# DW08B.net
KiCad netlist of a schematic drawn in EAGLE
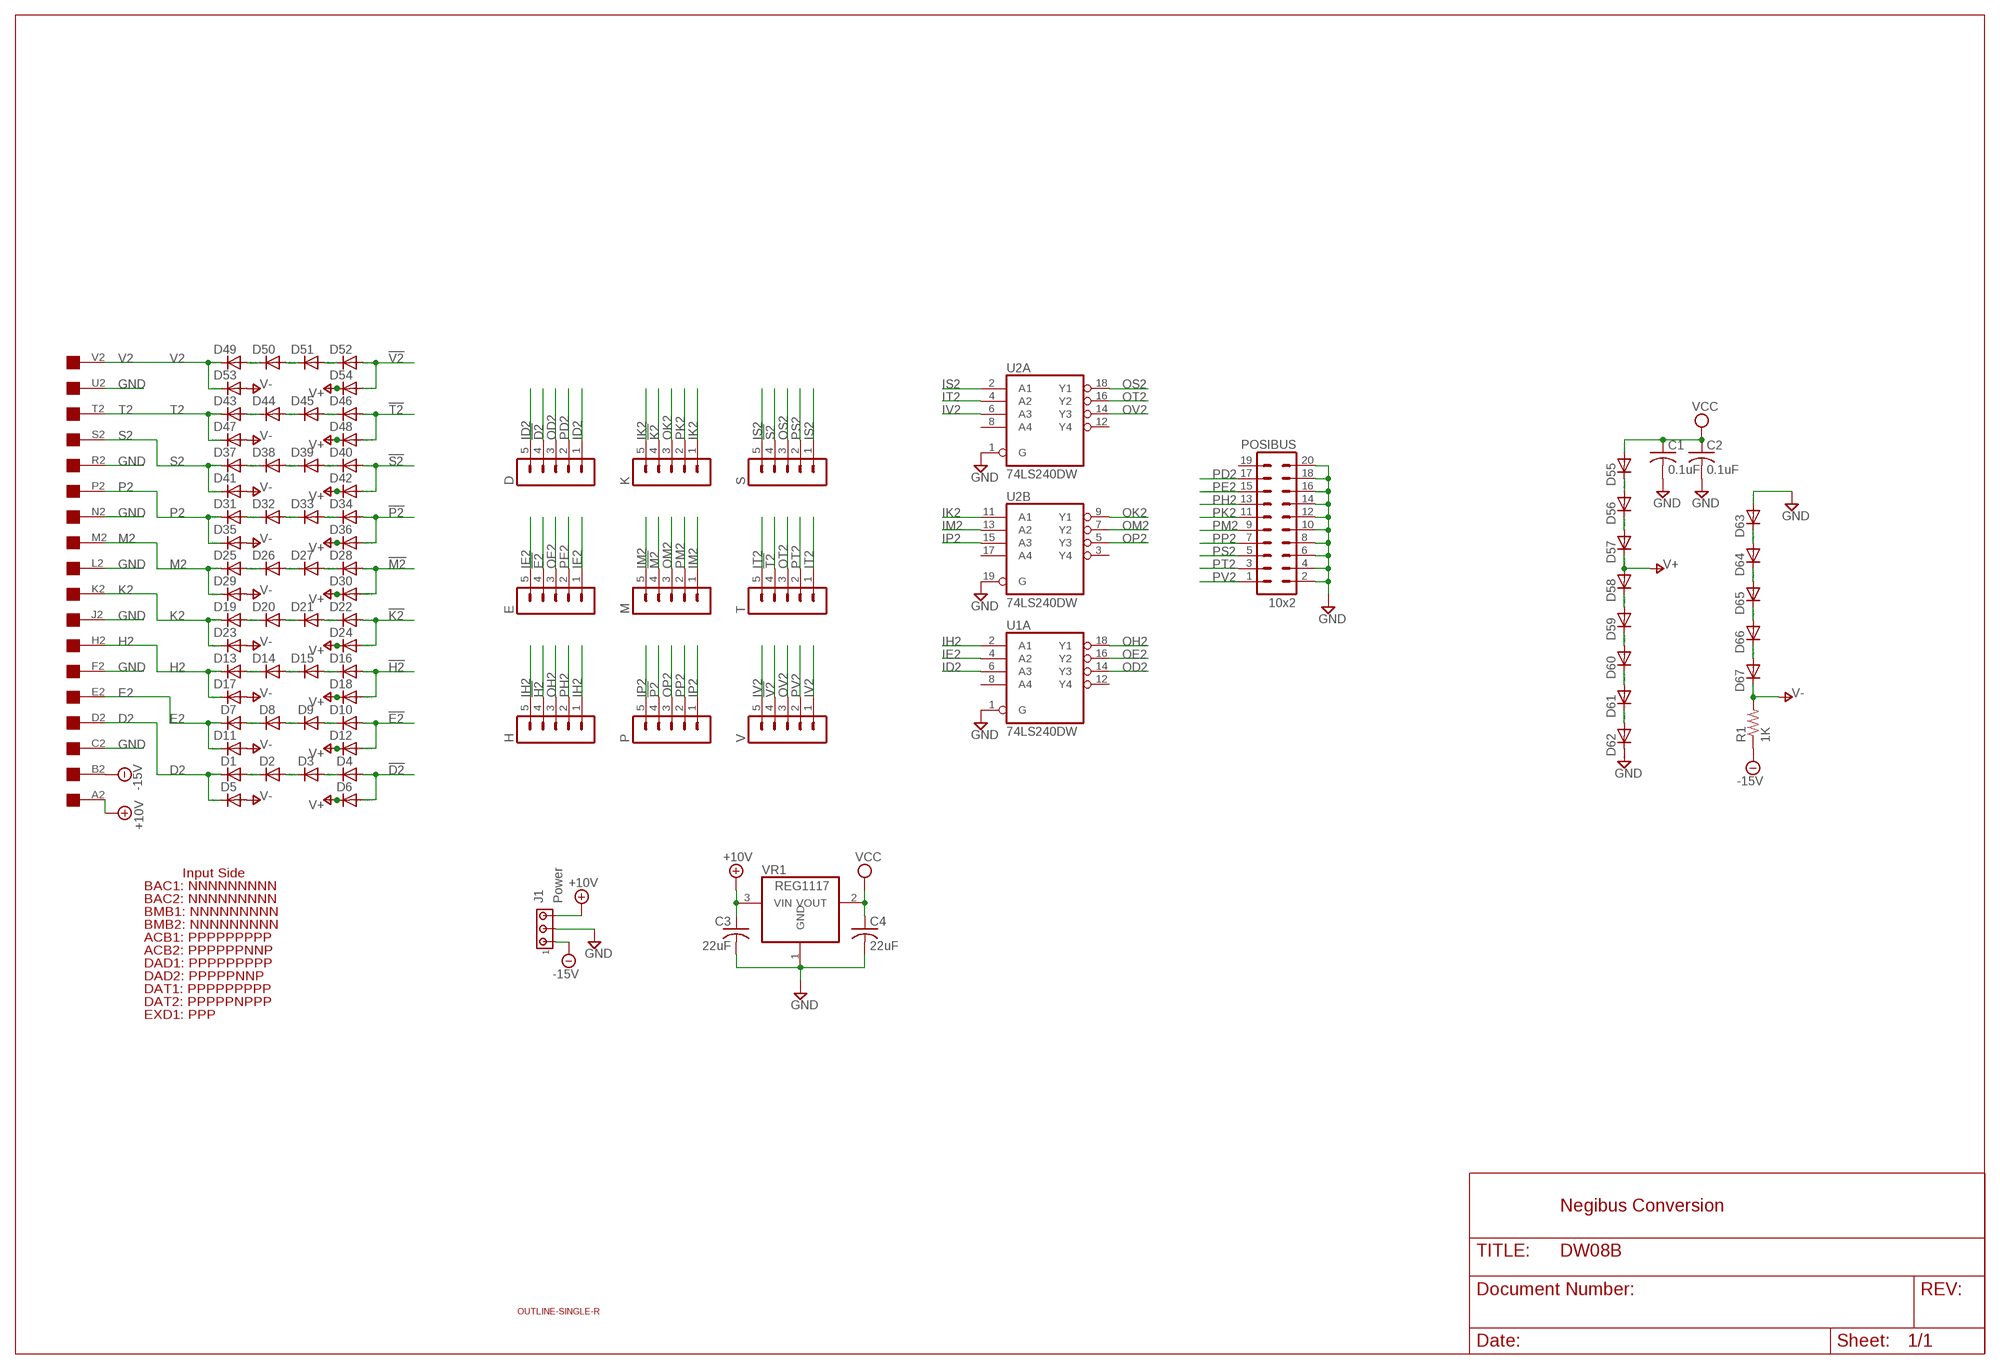
[diagram p0: schematic, sheet 1]

(export (version "E")
  (design (tool "Eeschema 10.0.6"))
  (components
    (comp (ref "C1")
      (value "0.1uF")
      (footprint "eagle-import:C050-025X075")
      (libsource (lib "eagle-import") (part "C-US050-025X075"))
    )
    (comp (ref "C2")
      (value "0.1uF")
      (footprint "eagle-import:C050-025X075")
      (libsource (lib "eagle-import") (part "C-US050-025X075"))
    )
    (comp (ref "C3")
      (value "22uF")
      (footprint "eagle-import:C0805")
      (libsource (lib "eagle-import") (part "C-USC0805"))
    )
    (comp (ref "C4")
      (value "22uF")
      (footprint "eagle-import:C0805")
      (libsource (lib "eagle-import") (part "C-USC0805"))
    )
    (comp (ref "D")
      (value "MA05-1")
      (footprint "eagle-import:MA05-1")
      (libsource (lib "eagle-import") (part "MA05-1"))
    )
    (comp (ref "D1")
      (value "1N4148WS")
      (footprint "eagle-import:SOD323-W")
      (libsource (lib "eagle-import") (part "DIODE-SOD323-W"))
    )
    (comp (ref "D2")
      (value "1N4148WS")
      (footprint "eagle-import:SOD323-W")
      (libsource (lib "eagle-import") (part "DIODE-SOD323-W"))
    )
    (comp (ref "D3")
      (value "1N4148WS")
      (footprint "eagle-import:SOD323-W")
      (libsource (lib "eagle-import") (part "DIODE-SOD323-W"))
    )
    (comp (ref "D4")
      (value "1N4148WS")
      (footprint "eagle-import:SOD323-W")
      (libsource (lib "eagle-import") (part "DIODE-SOD323-W"))
    )
    (comp (ref "D5")
      (value "1N4148WS")
      (footprint "eagle-import:SOD323-W")
      (libsource (lib "eagle-import") (part "DIODE-SOD323-W"))
    )
    (comp (ref "D6")
      (value "1N4148WS")
      (footprint "eagle-import:SOD323-W")
      (libsource (lib "eagle-import") (part "DIODE-SOD323-W"))
    )
    (comp (ref "D7")
      (value "1N4148WS")
      (footprint "eagle-import:SOD323-W")
      (libsource (lib "eagle-import") (part "DIODE-SOD323-W"))
    )
    (comp (ref "D8")
      (value "1N4148WS")
      (footprint "eagle-import:SOD323-W")
      (libsource (lib "eagle-import") (part "DIODE-SOD323-W"))
    )
    (comp (ref "D9")
      (value "1N4148WS")
      (footprint "eagle-import:SOD323-W")
      (libsource (lib "eagle-import") (part "DIODE-SOD323-W"))
    )
    (comp (ref "D10")
      (value "1N4148WS")
      (footprint "eagle-import:SOD323-W")
      (libsource (lib "eagle-import") (part "DIODE-SOD323-W"))
    )
    (comp (ref "D11")
      (value "1N4148WS")
      (footprint "eagle-import:SOD323-W")
      (libsource (lib "eagle-import") (part "DIODE-SOD323-W"))
    )
    (comp (ref "D12")
      (value "1N4148WS")
      (footprint "eagle-import:SOD323-W")
      (libsource (lib "eagle-import") (part "DIODE-SOD323-W"))
    )
    (comp (ref "D13")
      (value "1N4148WS")
      (footprint "eagle-import:SOD323-W")
      (libsource (lib "eagle-import") (part "DIODE-SOD323-W"))
    )
    (comp (ref "D14")
      (value "1N4148WS")
      (footprint "eagle-import:SOD323-W")
      (libsource (lib "eagle-import") (part "DIODE-SOD323-W"))
    )
    (comp (ref "D15")
      (value "1N4148WS")
      (footprint "eagle-import:SOD323-W")
      (libsource (lib "eagle-import") (part "DIODE-SOD323-W"))
    )
    (comp (ref "D16")
      (value "1N4148WS")
      (footprint "eagle-import:SOD323-W")
      (libsource (lib "eagle-import") (part "DIODE-SOD323-W"))
    )
    (comp (ref "D17")
      (value "1N4148WS")
      (footprint "eagle-import:SOD323-W")
      (libsource (lib "eagle-import") (part "DIODE-SOD323-W"))
    )
    (comp (ref "D18")
      (value "1N4148WS")
      (footprint "eagle-import:SOD323-W")
      (libsource (lib "eagle-import") (part "DIODE-SOD323-W"))
    )
    (comp (ref "D19")
      (value "1N4148WS")
      (footprint "eagle-import:SOD323-W")
      (libsource (lib "eagle-import") (part "DIODE-SOD323-W"))
    )
    (comp (ref "D20")
      (value "1N4148WS")
      (footprint "eagle-import:SOD323-W")
      (libsource (lib "eagle-import") (part "DIODE-SOD323-W"))
    )
    (comp (ref "D21")
      (value "1N4148WS")
      (footprint "eagle-import:SOD323-W")
      (libsource (lib "eagle-import") (part "DIODE-SOD323-W"))
    )
    (comp (ref "D22")
      (value "1N4148WS")
      (footprint "eagle-import:SOD323-W")
      (libsource (lib "eagle-import") (part "DIODE-SOD323-W"))
    )
    (comp (ref "D23")
      (value "1N4148WS")
      (footprint "eagle-import:SOD323-W")
      (libsource (lib "eagle-import") (part "DIODE-SOD323-W"))
    )
    (comp (ref "D24")
      (value "1N4148WS")
      (footprint "eagle-import:SOD323-W")
      (libsource (lib "eagle-import") (part "DIODE-SOD323-W"))
    )
    (comp (ref "D25")
      (value "1N4148WS")
      (footprint "eagle-import:SOD323-W")
      (libsource (lib "eagle-import") (part "DIODE-SOD323-W"))
    )
    (comp (ref "D26")
      (value "1N4148WS")
      (footprint "eagle-import:SOD323-W")
      (libsource (lib "eagle-import") (part "DIODE-SOD323-W"))
    )
    (comp (ref "D27")
      (value "1N4148WS")
      (footprint "eagle-import:SOD323-W")
      (libsource (lib "eagle-import") (part "DIODE-SOD323-W"))
    )
    (comp (ref "D28")
      (value "1N4148WS")
      (footprint "eagle-import:SOD323-W")
      (libsource (lib "eagle-import") (part "DIODE-SOD323-W"))
    )
    (comp (ref "D29")
      (value "1N4148WS")
      (footprint "eagle-import:SOD323-W")
      (libsource (lib "eagle-import") (part "DIODE-SOD323-W"))
    )
    (comp (ref "D30")
      (value "1N4148WS")
      (footprint "eagle-import:SOD323-W")
      (libsource (lib "eagle-import") (part "DIODE-SOD323-W"))
    )
    (comp (ref "D31")
      (value "1N4148WS")
      (footprint "eagle-import:SOD323-W")
      (libsource (lib "eagle-import") (part "DIODE-SOD323-W"))
    )
    (comp (ref "D32")
      (value "1N4148WS")
      (footprint "eagle-import:SOD323-W")
      (libsource (lib "eagle-import") (part "DIODE-SOD323-W"))
    )
    (comp (ref "D33")
      (value "1N4148WS")
      (footprint "eagle-import:SOD323-W")
      (libsource (lib "eagle-import") (part "DIODE-SOD323-W"))
    )
    (comp (ref "D34")
      (value "1N4148WS")
      (footprint "eagle-import:SOD323-W")
      (libsource (lib "eagle-import") (part "DIODE-SOD323-W"))
    )
    (comp (ref "D35")
      (value "1N4148WS")
      (footprint "eagle-import:SOD323-W")
      (libsource (lib "eagle-import") (part "DIODE-SOD323-W"))
    )
    (comp (ref "D36")
      (value "1N4148WS")
      (footprint "eagle-import:SOD323-W")
      (libsource (lib "eagle-import") (part "DIODE-SOD323-W"))
    )
    (comp (ref "D37")
      (value "1N4148WS")
      (footprint "eagle-import:SOD323-W")
      (libsource (lib "eagle-import") (part "DIODE-SOD323-W"))
    )
    (comp (ref "D38")
      (value "1N4148WS")
      (footprint "eagle-import:SOD323-W")
      (libsource (lib "eagle-import") (part "DIODE-SOD323-W"))
    )
    (comp (ref "D39")
      (value "1N4148WS")
      (footprint "eagle-import:SOD323-W")
      (libsource (lib "eagle-import") (part "DIODE-SOD323-W"))
    )
    (comp (ref "D40")
      (value "1N4148WS")
      (footprint "eagle-import:SOD323-W")
      (libsource (lib "eagle-import") (part "DIODE-SOD323-W"))
    )
    (comp (ref "D41")
      (value "1N4148WS")
      (footprint "eagle-import:SOD323-W")
      (libsource (lib "eagle-import") (part "DIODE-SOD323-W"))
    )
    (comp (ref "D42")
      (value "1N4148WS")
      (footprint "eagle-import:SOD323-W")
      (libsource (lib "eagle-import") (part "DIODE-SOD323-W"))
    )
    (comp (ref "D43")
      (value "1N4148WS")
      (footprint "eagle-import:SOD323-W")
      (libsource (lib "eagle-import") (part "DIODE-SOD323-W"))
    )
    (comp (ref "D44")
      (value "1N4148WS")
      (footprint "eagle-import:SOD323-W")
      (libsource (lib "eagle-import") (part "DIODE-SOD323-W"))
    )
    (comp (ref "D45")
      (value "1N4148WS")
      (footprint "eagle-import:SOD323-W")
      (libsource (lib "eagle-import") (part "DIODE-SOD323-W"))
    )
    (comp (ref "D46")
      (value "1N4148WS")
      (footprint "eagle-import:SOD323-W")
      (libsource (lib "eagle-import") (part "DIODE-SOD323-W"))
    )
    (comp (ref "D47")
      (value "1N4148WS")
      (footprint "eagle-import:SOD323-W")
      (libsource (lib "eagle-import") (part "DIODE-SOD323-W"))
    )
    (comp (ref "D48")
      (value "1N4148WS")
      (footprint "eagle-import:SOD323-W")
      (libsource (lib "eagle-import") (part "DIODE-SOD323-W"))
    )
    (comp (ref "D49")
      (value "1N4148WS")
      (footprint "eagle-import:SOD323-W")
      (libsource (lib "eagle-import") (part "DIODE-SOD323-W"))
    )
    (comp (ref "D50")
      (value "1N4148WS")
      (footprint "eagle-import:SOD323-W")
      (libsource (lib "eagle-import") (part "DIODE-SOD323-W"))
    )
    (comp (ref "D51")
      (value "1N4148WS")
      (footprint "eagle-import:SOD323-W")
      (libsource (lib "eagle-import") (part "DIODE-SOD323-W"))
    )
    (comp (ref "D52")
      (value "1N4148WS")
      (footprint "eagle-import:SOD323-W")
      (libsource (lib "eagle-import") (part "DIODE-SOD323-W"))
    )
    (comp (ref "D53")
      (value "1N4148WS")
      (footprint "eagle-import:SOD323-W")
      (libsource (lib "eagle-import") (part "DIODE-SOD323-W"))
    )
    (comp (ref "D54")
      (value "1N4148WS")
      (footprint "eagle-import:SOD323-W")
      (libsource (lib "eagle-import") (part "DIODE-SOD323-W"))
    )
    (comp (ref "D55")
      (value "1N4148WS")
      (footprint "eagle-import:SOD323-W")
      (libsource (lib "eagle-import") (part "DIODE-SOD323-W"))
    )
    (comp (ref "D56")
      (value "1N4148WS")
      (footprint "eagle-import:SOD323-W")
      (libsource (lib "eagle-import") (part "DIODE-SOD323-W"))
    )
    (comp (ref "D57")
      (value "1N4148WS")
      (footprint "eagle-import:SOD323-W")
      (libsource (lib "eagle-import") (part "DIODE-SOD323-W"))
    )
    (comp (ref "D58")
      (value "1N4148WS")
      (footprint "eagle-import:SOD323-W")
      (libsource (lib "eagle-import") (part "DIODE-SOD323-W"))
    )
    (comp (ref "D59")
      (value "1N4148WS")
      (footprint "eagle-import:SOD323-W")
      (libsource (lib "eagle-import") (part "DIODE-SOD323-W"))
    )
    (comp (ref "D60")
      (value "1N4148WS")
      (footprint "eagle-import:SOD323-W")
      (libsource (lib "eagle-import") (part "DIODE-SOD323-W"))
    )
    (comp (ref "D61")
      (value "1N4148WS")
      (footprint "eagle-import:SOD323-W")
      (libsource (lib "eagle-import") (part "DIODE-SOD323-W"))
    )
    (comp (ref "D62")
      (value "1N4148WS")
      (footprint "eagle-import:SOD323-W")
      (libsource (lib "eagle-import") (part "DIODE-SOD323-W"))
    )
    (comp (ref "D63")
      (value "1N4148WS")
      (footprint "eagle-import:SOD323-W")
      (libsource (lib "eagle-import") (part "DIODE-SOD323-W"))
    )
    (comp (ref "D64")
      (value "1N4148WS")
      (footprint "eagle-import:SOD323-W")
      (libsource (lib "eagle-import") (part "DIODE-SOD323-W"))
    )
    (comp (ref "D65")
      (value "1N4148WS")
      (footprint "eagle-import:SOD323-W")
      (libsource (lib "eagle-import") (part "DIODE-SOD323-W"))
    )
    (comp (ref "D66")
      (value "1N4148WS")
      (footprint "eagle-import:SOD323-W")
      (libsource (lib "eagle-import") (part "DIODE-SOD323-W"))
    )
    (comp (ref "D67")
      (value "1N4148WS")
      (footprint "eagle-import:SOD323-W")
      (libsource (lib "eagle-import") (part "DIODE-SOD323-W"))
    )
    (comp (ref "E")
      (value "MA05-1")
      (footprint "eagle-import:MA05-1")
      (libsource (lib "eagle-import") (part "MA05-1"))
    )
    (comp (ref "H")
      (value "MA05-1")
      (footprint "eagle-import:MA05-1")
      (libsource (lib "eagle-import") (part "MA05-1"))
    )
    (comp (ref "J1")
      (value "Power")
      (footprint "eagle-import:10X03MTA")
      (libsource (lib "eagle-import") (part "MTA03-100"))
    )
    (comp (ref "K")
      (value "MA05-1")
      (footprint "eagle-import:MA05-1")
      (libsource (lib "eagle-import") (part "MA05-1"))
    )
    (comp (ref "M")
      (value "MA05-1")
      (footprint "eagle-import:MA05-1")
      (libsource (lib "eagle-import") (part "MA05-1"))
    )
    (comp (ref "P")
      (value "MA05-1")
      (footprint "eagle-import:MA05-1")
      (libsource (lib "eagle-import") (part "MA05-1"))
    )
    (comp (ref "POSIBUS")
      (value "10x2")
      (footprint "eagle-import:MA10-2")
      (libsource (lib "eagle-import") (part "MA10-2"))
    )
    (comp (ref "R1")
      (value "1K")
      (footprint "eagle-import:0207_10")
      (libsource (lib "eagle-import") (part "R-US_0207/10"))
    )
    (comp (ref "S")
      (value "MA05-1")
      (footprint "eagle-import:MA05-1")
      (libsource (lib "eagle-import") (part "MA05-1"))
    )
    (comp (ref "T")
      (value "MA05-1")
      (footprint "eagle-import:MA05-1")
      (libsource (lib "eagle-import") (part "MA05-1"))
    )
    (comp (ref "U$1")
      (value "OUTLINE-SINGLE-R")
      (footprint "eagle-import:SINGLE-R")
      (libsource (lib "eagle-import") (part "OUTLINE-SINGLE-R"))
    )
    (comp (ref "U$2")
      (value "EDGE")
      (footprint "eagle-import:EDGE-CON2")
      (libsource (lib "eagle-import") (part "SINGLE"))
    )
    (comp (ref "U1")
      (value "74LS240DW")
      (footprint "eagle-import:SO20W")
      (libsource (lib "eagle-import") (part "74240DWLS"))
    )
    (comp (ref "U2")
      (value "74LS240DW")
      (footprint "eagle-import:SO20W")
      (libsource (lib "eagle-import") (part "74240DWLS"))
    )
    (comp (ref "V")
      (value "MA05-1")
      (footprint "eagle-import:MA05-1")
      (libsource (lib "eagle-import") (part "MA05-1"))
    )
    (comp (ref "VR1")
      (value "REG1117")
      (footprint "eagle-import:SOT223")
      (libsource (lib "eagle-import") (part "REG1117"))
    )
  )
  (nets
    (net (code "1") (name "+10V") (class "Default")
      (node (ref "C3") (pin "1") (pinfunction "1_1") (pintype "passive"))
      (node (ref "J1") (pin "3") (pinfunction "3_3") (pintype "passive"))
      (node (ref "U$2") (pin "A2") (pinfunction "1_A2") (pintype "bidirectional"))
      (node (ref "VR1") (pin "3") (pinfunction "VIN_3") (pintype "input"))
    )
    (net (code "2") (name "-15V") (class "Default")
      (node (ref "J1") (pin "1") (pinfunction "1_1") (pintype "passive"))
      (node (ref "R1") (pin "1") (pinfunction "1_1") (pintype "passive"))
      (node (ref "U$2") (pin "B2") (pinfunction "1_B2") (pintype "bidirectional"))
    )
    (net (code "3") (name "/D2") (class "Default")
      (node (ref "D1") (pin "C") (pinfunction "C_C") (pintype "passive"))
      (node (ref "D5") (pin "C") (pinfunction "C_C") (pintype "passive"))
      (node (ref "U$2") (pin "D2") (pinfunction "1_D2") (pintype "bidirectional"))
    )
    (net (code "4") (name "/E2") (class "Default")
      (node (ref "D11") (pin "C") (pinfunction "C_C") (pintype "passive"))
      (node (ref "D7") (pin "C") (pinfunction "C_C") (pintype "passive"))
      (node (ref "U$2") (pin "E2") (pinfunction "1_E2") (pintype "bidirectional"))
    )
    (net (code "5") (name "/H2") (class "Default")
      (node (ref "D13") (pin "C") (pinfunction "C_C") (pintype "passive"))
      (node (ref "D17") (pin "C") (pinfunction "C_C") (pintype "passive"))
      (node (ref "U$2") (pin "H2") (pinfunction "1_H2") (pintype "bidirectional"))
    )
    (net (code "6") (name "/ID2") (class "Default")
      (node (ref "D") (pin "1") (pinfunction "1_1") (pintype "passive"))
      (node (ref "D") (pin "5") (pinfunction "5_5") (pintype "passive"))
      (node (ref "U1") (pin "6") (pinfunction "A3_6") (pintype "input"))
    )
    (net (code "7") (name "/IE2") (class "Default")
      (node (ref "E") (pin "1") (pinfunction "1_1") (pintype "passive"))
      (node (ref "E") (pin "5") (pinfunction "5_5") (pintype "passive"))
      (node (ref "U1") (pin "4") (pinfunction "A2_4") (pintype "input"))
    )
    (net (code "8") (name "/IH2") (class "Default")
      (node (ref "H") (pin "1") (pinfunction "1_1") (pintype "passive"))
      (node (ref "H") (pin "5") (pinfunction "5_5") (pintype "passive"))
      (node (ref "U1") (pin "2") (pinfunction "A1_2") (pintype "input"))
    )
    (net (code "9") (name "/IK2") (class "Default")
      (node (ref "K") (pin "1") (pinfunction "1_1") (pintype "passive"))
      (node (ref "K") (pin "5") (pinfunction "5_5") (pintype "passive"))
      (node (ref "U2") (pin "11") (pinfunction "A1_11") (pintype "input"))
    )
    (net (code "10") (name "/IM2") (class "Default")
      (node (ref "M") (pin "1") (pinfunction "1_1") (pintype "passive"))
      (node (ref "M") (pin "5") (pinfunction "5_5") (pintype "passive"))
      (node (ref "U2") (pin "13") (pinfunction "A2_13") (pintype "input"))
    )
    (net (code "11") (name "/IP2") (class "Default")
      (node (ref "P") (pin "1") (pinfunction "1_1") (pintype "passive"))
      (node (ref "P") (pin "5") (pinfunction "5_5") (pintype "passive"))
      (node (ref "U2") (pin "15") (pinfunction "A3_15") (pintype "input"))
    )
    (net (code "12") (name "/IS2") (class "Default")
      (node (ref "S") (pin "1") (pinfunction "1_1") (pintype "passive"))
      (node (ref "S") (pin "5") (pinfunction "5_5") (pintype "passive"))
      (node (ref "U2") (pin "2") (pinfunction "A1_2") (pintype "input"))
    )
    (net (code "13") (name "/IT2") (class "Default")
      (node (ref "T") (pin "1") (pinfunction "1_1") (pintype "passive"))
      (node (ref "T") (pin "5") (pinfunction "5_5") (pintype "passive"))
      (node (ref "U2") (pin "4") (pinfunction "A2_4") (pintype "input"))
    )
    (net (code "14") (name "/IV2") (class "Default")
      (node (ref "U2") (pin "6") (pinfunction "A3_6") (pintype "input"))
      (node (ref "V") (pin "1") (pinfunction "1_1") (pintype "passive"))
      (node (ref "V") (pin "5") (pinfunction "5_5") (pintype "passive"))
    )
    (net (code "15") (name "/K2") (class "Default")
      (node (ref "D19") (pin "C") (pinfunction "C_C") (pintype "passive"))
      (node (ref "D23") (pin "C") (pinfunction "C_C") (pintype "passive"))
      (node (ref "U$2") (pin "K2") (pinfunction "1_K2") (pintype "bidirectional"))
    )
    (net (code "16") (name "/M2") (class "Default")
      (node (ref "D25") (pin "C") (pinfunction "C_C") (pintype "passive"))
      (node (ref "D29") (pin "C") (pinfunction "C_C") (pintype "passive"))
      (node (ref "U$2") (pin "M2") (pinfunction "1_M2") (pintype "bidirectional"))
    )
    (net (code "17") (name "/OD2") (class "Default")
      (node (ref "D") (pin "3") (pinfunction "3_3") (pintype "passive"))
      (node (ref "U1") (pin "14") (pinfunction "Y3_14") (pintype "tri_state"))
    )
    (net (code "18") (name "/OE2") (class "Default")
      (node (ref "E") (pin "3") (pinfunction "3_3") (pintype "passive"))
      (node (ref "U1") (pin "16") (pinfunction "Y2_16") (pintype "tri_state"))
    )
    (net (code "19") (name "/OH2") (class "Default")
      (node (ref "H") (pin "3") (pinfunction "3_3") (pintype "passive"))
      (node (ref "U1") (pin "18") (pinfunction "Y1_18") (pintype "tri_state"))
    )
    (net (code "20") (name "/OK2") (class "Default")
      (node (ref "K") (pin "3") (pinfunction "3_3") (pintype "passive"))
      (node (ref "U2") (pin "9") (pinfunction "Y1_9") (pintype "tri_state"))
    )
    (net (code "21") (name "/OM2") (class "Default")
      (node (ref "M") (pin "3") (pinfunction "3_3") (pintype "passive"))
      (node (ref "U2") (pin "7") (pinfunction "Y2_7") (pintype "tri_state"))
    )
    (net (code "22") (name "/OP2") (class "Default")
      (node (ref "P") (pin "3") (pinfunction "3_3") (pintype "passive"))
      (node (ref "U2") (pin "5") (pinfunction "Y3_5") (pintype "tri_state"))
    )
    (net (code "23") (name "/OS2") (class "Default")
      (node (ref "S") (pin "3") (pinfunction "3_3") (pintype "passive"))
      (node (ref "U2") (pin "18") (pinfunction "Y1_18") (pintype "tri_state"))
    )
    (net (code "24") (name "/OT2") (class "Default")
      (node (ref "T") (pin "3") (pinfunction "3_3") (pintype "passive"))
      (node (ref "U2") (pin "16") (pinfunction "Y2_16") (pintype "tri_state"))
    )
    (net (code "25") (name "/OV2") (class "Default")
      (node (ref "U2") (pin "14") (pinfunction "Y3_14") (pintype "tri_state"))
      (node (ref "V") (pin "3") (pinfunction "3_3") (pintype "passive"))
    )
    (net (code "26") (name "/P2") (class "Default")
      (node (ref "D31") (pin "C") (pinfunction "C_C") (pintype "passive"))
      (node (ref "D35") (pin "C") (pinfunction "C_C") (pintype "passive"))
      (node (ref "U$2") (pin "P2") (pinfunction "1_P2") (pintype "bidirectional"))
    )
    (net (code "27") (name "/PD2") (class "Default")
      (node (ref "D") (pin "2") (pinfunction "2_2") (pintype "passive"))
      (node (ref "POSIBUS") (pin "17") (pinfunction "17_17") (pintype "passive"))
    )
    (net (code "28") (name "/PE2") (class "Default")
      (node (ref "E") (pin "2") (pinfunction "2_2") (pintype "passive"))
      (node (ref "POSIBUS") (pin "15") (pinfunction "15_15") (pintype "passive"))
    )
    (net (code "29") (name "/PH2") (class "Default")
      (node (ref "H") (pin "2") (pinfunction "2_2") (pintype "passive"))
      (node (ref "POSIBUS") (pin "13") (pinfunction "13_13") (pintype "passive"))
    )
    (net (code "30") (name "/PK2") (class "Default")
      (node (ref "K") (pin "2") (pinfunction "2_2") (pintype "passive"))
      (node (ref "POSIBUS") (pin "11") (pinfunction "11_11") (pintype "passive"))
    )
    (net (code "31") (name "/PM2") (class "Default")
      (node (ref "M") (pin "2") (pinfunction "2_2") (pintype "passive"))
      (node (ref "POSIBUS") (pin "9") (pinfunction "9_9") (pintype "passive"))
    )
    (net (code "32") (name "/PP2") (class "Default")
      (node (ref "P") (pin "2") (pinfunction "2_2") (pintype "passive"))
      (node (ref "POSIBUS") (pin "7") (pinfunction "7_7") (pintype "passive"))
    )
    (net (code "33") (name "/PS2") (class "Default")
      (node (ref "POSIBUS") (pin "5") (pinfunction "5_5") (pintype "passive"))
      (node (ref "S") (pin "2") (pinfunction "2_2") (pintype "passive"))
    )
    (net (code "34") (name "/PT2") (class "Default")
      (node (ref "POSIBUS") (pin "3") (pinfunction "3_3") (pintype "passive"))
      (node (ref "T") (pin "2") (pinfunction "2_2") (pintype "passive"))
    )
    (net (code "35") (name "/PV2") (class "Default")
      (node (ref "POSIBUS") (pin "1") (pinfunction "1_1") (pintype "passive"))
      (node (ref "V") (pin "2") (pinfunction "2_2") (pintype "passive"))
    )
    (net (code "36") (name "/S2") (class "Default")
      (node (ref "D37") (pin "C") (pinfunction "C_C") (pintype "passive"))
      (node (ref "D41") (pin "C") (pinfunction "C_C") (pintype "passive"))
      (node (ref "U$2") (pin "S2") (pinfunction "1_S2") (pintype "bidirectional"))
    )
    (net (code "37") (name "/T2") (class "Default")
      (node (ref "D43") (pin "C") (pinfunction "C_C") (pintype "passive"))
      (node (ref "D47") (pin "C") (pinfunction "C_C") (pintype "passive"))
      (node (ref "U$2") (pin "T2") (pinfunction "1_T2") (pintype "bidirectional"))
    )
    (net (code "38") (name "/V2") (class "Default")
      (node (ref "D49") (pin "C") (pinfunction "C_C") (pintype "passive"))
      (node (ref "D53") (pin "C") (pinfunction "C_C") (pintype "passive"))
      (node (ref "U$2") (pin "V2") (pinfunction "1_V2") (pintype "bidirectional"))
    )
    (net (code "39") (name "/~{D2}") (class "Default")
      (node (ref "D") (pin "4") (pinfunction "4_4") (pintype "passive"))
      (node (ref "D4") (pin "A") (pinfunction "A_A") (pintype "passive"))
      (node (ref "D6") (pin "A") (pinfunction "A_A") (pintype "passive"))
    )
    (net (code "40") (name "/~{E2}") (class "Default")
      (node (ref "D10") (pin "A") (pinfunction "A_A") (pintype "passive"))
      (node (ref "D12") (pin "A") (pinfunction "A_A") (pintype "passive"))
      (node (ref "E") (pin "4") (pinfunction "4_4") (pintype "passive"))
    )
    (net (code "41") (name "/~{H2}") (class "Default")
      (node (ref "D16") (pin "A") (pinfunction "A_A") (pintype "passive"))
      (node (ref "D18") (pin "A") (pinfunction "A_A") (pintype "passive"))
      (node (ref "H") (pin "4") (pinfunction "4_4") (pintype "passive"))
    )
    (net (code "42") (name "/~{K2}") (class "Default")
      (node (ref "D22") (pin "A") (pinfunction "A_A") (pintype "passive"))
      (node (ref "D24") (pin "A") (pinfunction "A_A") (pintype "passive"))
      (node (ref "K") (pin "4") (pinfunction "4_4") (pintype "passive"))
    )
    (net (code "43") (name "/~{M2}") (class "Default")
      (node (ref "D28") (pin "A") (pinfunction "A_A") (pintype "passive"))
      (node (ref "D30") (pin "A") (pinfunction "A_A") (pintype "passive"))
      (node (ref "M") (pin "4") (pinfunction "4_4") (pintype "passive"))
    )
    (net (code "44") (name "/~{P2}") (class "Default")
      (node (ref "D34") (pin "A") (pinfunction "A_A") (pintype "passive"))
      (node (ref "D36") (pin "A") (pinfunction "A_A") (pintype "passive"))
      (node (ref "P") (pin "4") (pinfunction "4_4") (pintype "passive"))
    )
    (net (code "45") (name "/~{S2}") (class "Default")
      (node (ref "D40") (pin "A") (pinfunction "A_A") (pintype "passive"))
      (node (ref "D42") (pin "A") (pinfunction "A_A") (pintype "passive"))
      (node (ref "S") (pin "4") (pinfunction "4_4") (pintype "passive"))
    )
    (net (code "46") (name "/~{T2}") (class "Default")
      (node (ref "D46") (pin "A") (pinfunction "A_A") (pintype "passive"))
      (node (ref "D48") (pin "A") (pinfunction "A_A") (pintype "passive"))
      (node (ref "T") (pin "4") (pinfunction "4_4") (pintype "passive"))
    )
    (net (code "47") (name "/~{V2}") (class "Default")
      (node (ref "D52") (pin "A") (pinfunction "A_A") (pintype "passive"))
      (node (ref "D54") (pin "A") (pinfunction "A_A") (pintype "passive"))
      (node (ref "V") (pin "4") (pinfunction "4_4") (pintype "passive"))
    )
    (net (code "48") (name "GND") (class "Default")
      (node (ref "C1") (pin "2") (pinfunction "2_2") (pintype "passive"))
      (node (ref "C2") (pin "2") (pinfunction "2_2") (pintype "passive"))
      (node (ref "C3") (pin "2") (pinfunction "2_2") (pintype "passive"))
      (node (ref "C4") (pin "2") (pinfunction "2_2") (pintype "passive"))
      (node (ref "D62") (pin "C") (pinfunction "C_C") (pintype "passive"))
      (node (ref "D63") (pin "A") (pinfunction "A_A") (pintype "passive"))
      (node (ref "J1") (pin "2") (pinfunction "2_2") (pintype "passive"))
      (node (ref "POSIBUS") (pin "10") (pinfunction "10_10") (pintype "passive"))
      (node (ref "POSIBUS") (pin "12") (pinfunction "12_12") (pintype "passive"))
      (node (ref "POSIBUS") (pin "14") (pinfunction "14_14") (pintype "passive"))
      (node (ref "POSIBUS") (pin "16") (pinfunction "16_16") (pintype "passive"))
      (node (ref "POSIBUS") (pin "18") (pinfunction "18_18") (pintype "passive"))
      (node (ref "POSIBUS") (pin "2") (pinfunction "2_2") (pintype "passive"))
      (node (ref "POSIBUS") (pin "20") (pinfunction "20_20") (pintype "passive"))
      (node (ref "POSIBUS") (pin "4") (pinfunction "4_4") (pintype "passive"))
      (node (ref "POSIBUS") (pin "6") (pinfunction "6_6") (pintype "passive"))
      (node (ref "POSIBUS") (pin "8") (pinfunction "8_8") (pintype "passive"))
      (node (ref "U$2") (pin "C2") (pinfunction "1_C2") (pintype "bidirectional"))
      (node (ref "U$2") (pin "F2") (pinfunction "1_F2") (pintype "bidirectional"))
      (node (ref "U$2") (pin "J2") (pinfunction "1_J2") (pintype "bidirectional"))
      (node (ref "U$2") (pin "L2") (pinfunction "1_L2") (pintype "bidirectional"))
      (node (ref "U$2") (pin "N2") (pinfunction "1_N2") (pintype "bidirectional"))
      (node (ref "U$2") (pin "R2") (pinfunction "1_R2") (pintype "bidirectional"))
      (node (ref "U$2") (pin "U2") (pinfunction "1_U2") (pintype "bidirectional"))
      (node (ref "U1") (pin "1") (pinfunction "G_1") (pintype "input"))
      (node (ref "U2") (pin "1") (pinfunction "G_1") (pintype "input"))
      (node (ref "U2") (pin "19") (pinfunction "G_19") (pintype "input"))
      (node (ref "VR1") (pin "1") (pinfunction "GND_1") (pintype "power_in"))
    )
    (net (code "49") (name "Net-(D1-PadA)") (class "Default")
      (node (ref "D1") (pin "A") (pinfunction "A_A") (pintype "passive"))
      (node (ref "D2") (pin "C") (pinfunction "C_C") (pintype "passive"))
    )
    (net (code "50") (name "Net-(D2-PadA)") (class "Default")
      (node (ref "D2") (pin "A") (pinfunction "A_A") (pintype "passive"))
      (node (ref "D3") (pin "C") (pinfunction "C_C") (pintype "passive"))
    )
    (net (code "51") (name "Net-(D3-PadA)") (class "Default")
      (node (ref "D3") (pin "A") (pinfunction "A_A") (pintype "passive"))
      (node (ref "D4") (pin "C") (pinfunction "C_C") (pintype "passive"))
    )
    (net (code "52") (name "Net-(D7-PadA)") (class "Default")
      (node (ref "D7") (pin "A") (pinfunction "A_A") (pintype "passive"))
      (node (ref "D8") (pin "C") (pinfunction "C_C") (pintype "passive"))
    )
    (net (code "53") (name "Net-(D8-PadA)") (class "Default")
      (node (ref "D8") (pin "A") (pinfunction "A_A") (pintype "passive"))
      (node (ref "D9") (pin "C") (pinfunction "C_C") (pintype "passive"))
    )
    (net (code "54") (name "Net-(D10-PadC)") (class "Default")
      (node (ref "D10") (pin "C") (pinfunction "C_C") (pintype "passive"))
      (node (ref "D9") (pin "A") (pinfunction "A_A") (pintype "passive"))
    )
    (net (code "55") (name "Net-(D13-PadA)") (class "Default")
      (node (ref "D13") (pin "A") (pinfunction "A_A") (pintype "passive"))
      (node (ref "D14") (pin "C") (pinfunction "C_C") (pintype "passive"))
    )
    (net (code "56") (name "Net-(D14-PadA)") (class "Default")
      (node (ref "D14") (pin "A") (pinfunction "A_A") (pintype "passive"))
      (node (ref "D15") (pin "C") (pinfunction "C_C") (pintype "passive"))
    )
    (net (code "57") (name "Net-(D15-PadA)") (class "Default")
      (node (ref "D15") (pin "A") (pinfunction "A_A") (pintype "passive"))
      (node (ref "D16") (pin "C") (pinfunction "C_C") (pintype "passive"))
    )
    (net (code "58") (name "Net-(D19-PadA)") (class "Default")
      (node (ref "D19") (pin "A") (pinfunction "A_A") (pintype "passive"))
      (node (ref "D20") (pin "C") (pinfunction "C_C") (pintype "passive"))
    )
    (net (code "59") (name "Net-(D20-PadA)") (class "Default")
      (node (ref "D20") (pin "A") (pinfunction "A_A") (pintype "passive"))
      (node (ref "D21") (pin "C") (pinfunction "C_C") (pintype "passive"))
    )
    (net (code "60") (name "Net-(D21-PadA)") (class "Default")
      (node (ref "D21") (pin "A") (pinfunction "A_A") (pintype "passive"))
      (node (ref "D22") (pin "C") (pinfunction "C_C") (pintype "passive"))
    )
    (net (code "61") (name "Net-(D25-PadA)") (class "Default")
      (node (ref "D25") (pin "A") (pinfunction "A_A") (pintype "passive"))
      (node (ref "D26") (pin "C") (pinfunction "C_C") (pintype "passive"))
    )
    (net (code "62") (name "Net-(D26-PadA)") (class "Default")
      (node (ref "D26") (pin "A") (pinfunction "A_A") (pintype "passive"))
      (node (ref "D27") (pin "C") (pinfunction "C_C") (pintype "passive"))
    )
    (net (code "63") (name "Net-(D27-PadA)") (class "Default")
      (node (ref "D27") (pin "A") (pinfunction "A_A") (pintype "passive"))
      (node (ref "D28") (pin "C") (pinfunction "C_C") (pintype "passive"))
    )
    (net (code "64") (name "Net-(D31-PadA)") (class "Default")
      (node (ref "D31") (pin "A") (pinfunction "A_A") (pintype "passive"))
      (node (ref "D32") (pin "C") (pinfunction "C_C") (pintype "passive"))
    )
    (net (code "65") (name "Net-(D32-PadA)") (class "Default")
      (node (ref "D32") (pin "A") (pinfunction "A_A") (pintype "passive"))
      (node (ref "D33") (pin "C") (pinfunction "C_C") (pintype "passive"))
    )
    (net (code "66") (name "Net-(D33-PadA)") (class "Default")
      (node (ref "D33") (pin "A") (pinfunction "A_A") (pintype "passive"))
      (node (ref "D34") (pin "C") (pinfunction "C_C") (pintype "passive"))
    )
    (net (code "67") (name "Net-(D37-PadA)") (class "Default")
      (node (ref "D37") (pin "A") (pinfunction "A_A") (pintype "passive"))
      (node (ref "D38") (pin "C") (pinfunction "C_C") (pintype "passive"))
    )
    (net (code "68") (name "Net-(D38-PadA)") (class "Default")
      (node (ref "D38") (pin "A") (pinfunction "A_A") (pintype "passive"))
      (node (ref "D39") (pin "C") (pinfunction "C_C") (pintype "passive"))
    )
    (net (code "69") (name "Net-(D39-PadA)") (class "Default")
      (node (ref "D39") (pin "A") (pinfunction "A_A") (pintype "passive"))
      (node (ref "D40") (pin "C") (pinfunction "C_C") (pintype "passive"))
    )
    (net (code "70") (name "Net-(D43-PadA)") (class "Default")
      (node (ref "D43") (pin "A") (pinfunction "A_A") (pintype "passive"))
      (node (ref "D44") (pin "C") (pinfunction "C_C") (pintype "passive"))
    )
    (net (code "71") (name "Net-(D44-PadA)") (class "Default")
      (node (ref "D44") (pin "A") (pinfunction "A_A") (pintype "passive"))
      (node (ref "D45") (pin "C") (pinfunction "C_C") (pintype "passive"))
    )
    (net (code "72") (name "Net-(D45-PadA)") (class "Default")
      (node (ref "D45") (pin "A") (pinfunction "A_A") (pintype "passive"))
      (node (ref "D46") (pin "C") (pinfunction "C_C") (pintype "passive"))
    )
    (net (code "73") (name "Net-(D49-PadA)") (class "Default")
      (node (ref "D49") (pin "A") (pinfunction "A_A") (pintype "passive"))
      (node (ref "D50") (pin "C") (pinfunction "C_C") (pintype "passive"))
    )
    (net (code "74") (name "Net-(D50-PadA)") (class "Default")
      (node (ref "D50") (pin "A") (pinfunction "A_A") (pintype "passive"))
      (node (ref "D51") (pin "C") (pinfunction "C_C") (pintype "passive"))
    )
    (net (code "75") (name "Net-(D51-PadA)") (class "Default")
      (node (ref "D51") (pin "A") (pinfunction "A_A") (pintype "passive"))
      (node (ref "D52") (pin "C") (pinfunction "C_C") (pintype "passive"))
    )
    (net (code "76") (name "Net-(D55-PadC)") (class "Default")
      (node (ref "D55") (pin "C") (pinfunction "C_C") (pintype "passive"))
      (node (ref "D56") (pin "A") (pinfunction "A_A") (pintype "passive"))
    )
    (net (code "77") (name "Net-(D56-PadC)") (class "Default")
      (node (ref "D56") (pin "C") (pinfunction "C_C") (pintype "passive"))
      (node (ref "D57") (pin "A") (pinfunction "A_A") (pintype "passive"))
    )
    (net (code "78") (name "Net-(D58-PadC)") (class "Default")
      (node (ref "D58") (pin "C") (pinfunction "C_C") (pintype "passive"))
      (node (ref "D59") (pin "A") (pinfunction "A_A") (pintype "passive"))
    )
    (net (code "79") (name "Net-(D59-PadC)") (class "Default")
      (node (ref "D59") (pin "C") (pinfunction "C_C") (pintype "passive"))
      (node (ref "D60") (pin "A") (pinfunction "A_A") (pintype "passive"))
    )
    (net (code "80") (name "Net-(D60-PadC)") (class "Default")
      (node (ref "D60") (pin "C") (pinfunction "C_C") (pintype "passive"))
      (node (ref "D61") (pin "A") (pinfunction "A_A") (pintype "passive"))
    )
    (net (code "81") (name "Net-(D61-PadC)") (class "Default")
      (node (ref "D61") (pin "C") (pinfunction "C_C") (pintype "passive"))
      (node (ref "D62") (pin "A") (pinfunction "A_A") (pintype "passive"))
    )
    (net (code "82") (name "Net-(D63-PadC)") (class "Default")
      (node (ref "D63") (pin "C") (pinfunction "C_C") (pintype "passive"))
      (node (ref "D64") (pin "A") (pinfunction "A_A") (pintype "passive"))
    )
    (net (code "83") (name "Net-(D64-PadC)") (class "Default")
      (node (ref "D64") (pin "C") (pinfunction "C_C") (pintype "passive"))
      (node (ref "D65") (pin "A") (pinfunction "A_A") (pintype "passive"))
    )
    (net (code "84") (name "Net-(D65-PadC)") (class "Default")
      (node (ref "D65") (pin "C") (pinfunction "C_C") (pintype "passive"))
      (node (ref "D66") (pin "A") (pinfunction "A_A") (pintype "passive"))
    )
    (net (code "85") (name "Net-(D66-PadC)") (class "Default")
      (node (ref "D66") (pin "C") (pinfunction "C_C") (pintype "passive"))
      (node (ref "D67") (pin "A") (pinfunction "A_A") (pintype "passive"))
    )
    (net (code "86") (name "V+") (class "Default")
      (node (ref "D12") (pin "C") (pinfunction "C_C") (pintype "passive"))
      (node (ref "D18") (pin "C") (pinfunction "C_C") (pintype "passive"))
      (node (ref "D24") (pin "C") (pinfunction "C_C") (pintype "passive"))
      (node (ref "D30") (pin "C") (pinfunction "C_C") (pintype "passive"))
      (node (ref "D36") (pin "C") (pinfunction "C_C") (pintype "passive"))
      (node (ref "D42") (pin "C") (pinfunction "C_C") (pintype "passive"))
      (node (ref "D48") (pin "C") (pinfunction "C_C") (pintype "passive"))
      (node (ref "D54") (pin "C") (pinfunction "C_C") (pintype "passive"))
      (node (ref "D57") (pin "C") (pinfunction "C_C") (pintype "passive"))
      (node (ref "D58") (pin "A") (pinfunction "A_A") (pintype "passive"))
      (node (ref "D6") (pin "C") (pinfunction "C_C") (pintype "passive"))
    )
    (net (code "87") (name "V-") (class "Default")
      (node (ref "D11") (pin "A") (pinfunction "A_A") (pintype "passive"))
      (node (ref "D17") (pin "A") (pinfunction "A_A") (pintype "passive"))
      (node (ref "D23") (pin "A") (pinfunction "A_A") (pintype "passive"))
      (node (ref "D29") (pin "A") (pinfunction "A_A") (pintype "passive"))
      (node (ref "D35") (pin "A") (pinfunction "A_A") (pintype "passive"))
      (node (ref "D41") (pin "A") (pinfunction "A_A") (pintype "passive"))
      (node (ref "D47") (pin "A") (pinfunction "A_A") (pintype "passive"))
      (node (ref "D5") (pin "A") (pinfunction "A_A") (pintype "passive"))
      (node (ref "D53") (pin "A") (pinfunction "A_A") (pintype "passive"))
      (node (ref "D67") (pin "C") (pinfunction "C_C") (pintype "passive"))
      (node (ref "R1") (pin "2") (pinfunction "2_2") (pintype "passive"))
    )
    (net (code "88") (name "VCC") (class "Default")
      (node (ref "C1") (pin "1") (pinfunction "1_1") (pintype "passive"))
      (node (ref "C2") (pin "1") (pinfunction "1_1") (pintype "passive"))
      (node (ref "C4") (pin "1") (pinfunction "1_1") (pintype "passive"))
      (node (ref "D55") (pin "A") (pinfunction "A_A") (pintype "passive"))
      (node (ref "VR1") (pin "2") (pinfunction "VOUT_2") (pintype "output"))
    )
    (net (code "89") (name "unconnected-(POSIBUS-Pad19)") (class "Default")
      (node (ref "POSIBUS") (pin "19") (pinfunction "19_19") (pintype "passive"))
    )
    (net (code "90") (name "unconnected-(U1A-A4-Pad8)") (class "Default")
      (node (ref "U1") (pin "8") (pinfunction "A4_8") (pintype "input"))
    )
    (net (code "91") (name "unconnected-(U1A-Y4-Pad12)") (class "Default")
      (node (ref "U1") (pin "12") (pinfunction "Y4_12") (pintype "tri_state"))
    )
    (net (code "92") (name "unconnected-(U2A-A4-Pad8)") (class "Default")
      (node (ref "U2") (pin "8") (pinfunction "A4_8") (pintype "input"))
    )
    (net (code "93") (name "unconnected-(U2A-Y4-Pad12)") (class "Default")
      (node (ref "U2") (pin "12") (pinfunction "Y4_12") (pintype "tri_state"))
    )
    (net (code "94") (name "unconnected-(U2B-A4-Pad17)") (class "Default")
      (node (ref "U2") (pin "17") (pinfunction "A4_17") (pintype "input"))
    )
    (net (code "95") (name "unconnected-(U2B-Y4-Pad3)") (class "Default")
      (node (ref "U2") (pin "3") (pinfunction "Y4_3") (pintype "tri_state"))
    )
  )
)
